# Booster1.net
KiCad netlist of a schematic drawn in EAGLE
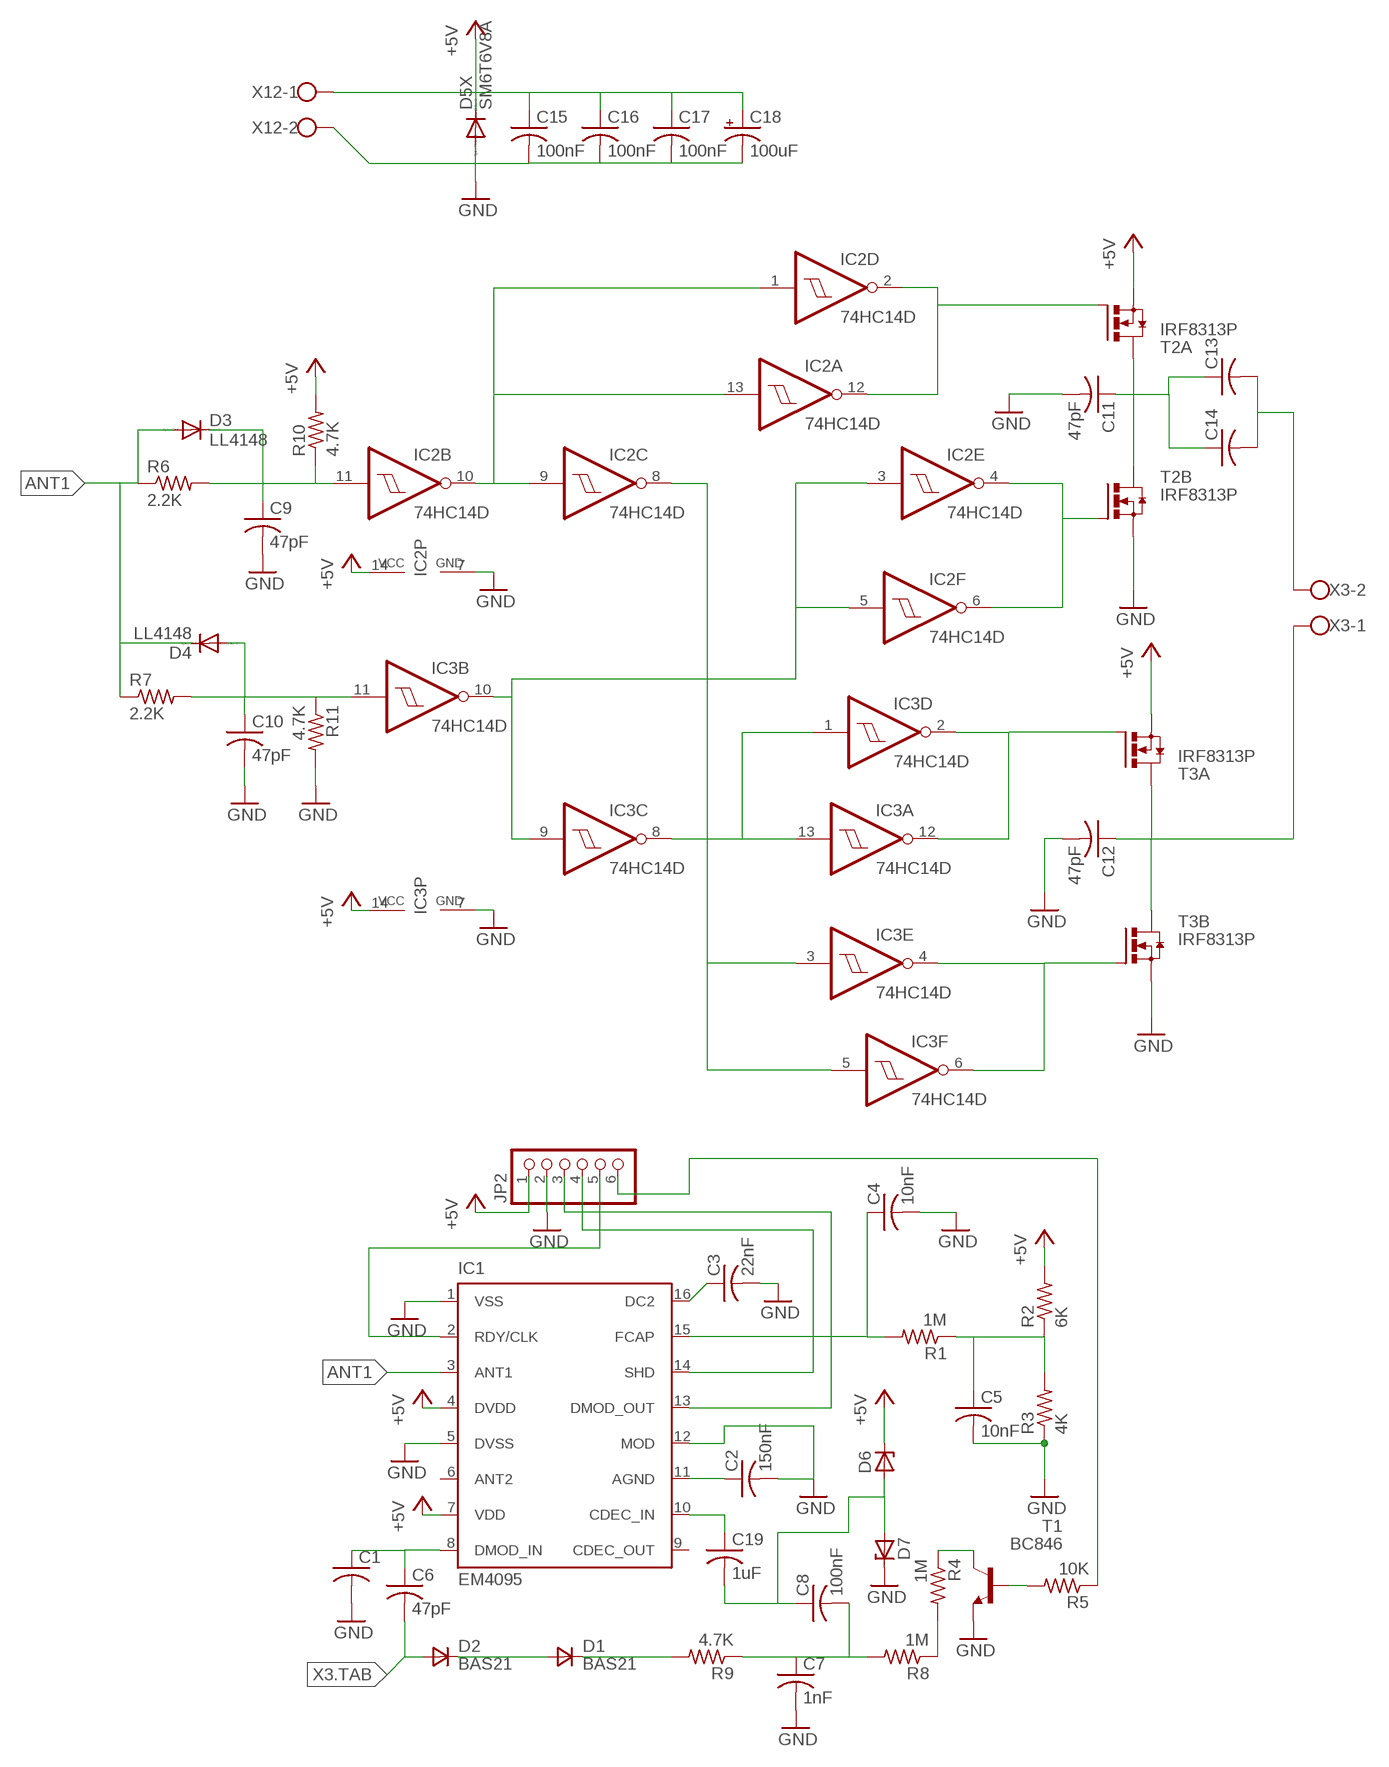
[diagram p0: schematic, sheet 1]

(export (version "E")
  (design (tool "Eeschema 10.0.6"))
  (components
    (comp (ref "C1")
      (value "C-USC1206K")
      (footprint "eagle-import:C1206K")
      (libsource (lib "eagle-import") (part "C-USC1206K"))
    )
    (comp (ref "C2")
      (value "150nF")
      (footprint "eagle-import:C1206")
      (libsource (lib "eagle-import") (part "C-USC1206"))
    )
    (comp (ref "C3")
      (value "22nF")
      (footprint "eagle-import:C1206K")
      (libsource (lib "eagle-import") (part "C-USC1206K"))
    )
    (comp (ref "C4")
      (value "10nF")
      (footprint "eagle-import:C1206K")
      (libsource (lib "eagle-import") (part "C-USC1206K"))
    )
    (comp (ref "C5")
      (value "10nF")
      (footprint "eagle-import:C1206K")
      (libsource (lib "eagle-import") (part "C-USC1206K"))
    )
    (comp (ref "C6")
      (value "47pF")
      (footprint "eagle-import:C050-025X075")
      (libsource (lib "eagle-import") (part "C-US050-025X075"))
    )
    (comp (ref "C7")
      (value "1nF")
      (footprint "eagle-import:C050-025X075")
      (libsource (lib "eagle-import") (part "C-US050-025X075"))
    )
    (comp (ref "C8")
      (value "100nF")
      (footprint "eagle-import:C050-025X075")
      (libsource (lib "eagle-import") (part "C-US050-025X075"))
    )
    (comp (ref "C9")
      (value "47pF")
      (footprint "eagle-import:C1206")
      (libsource (lib "eagle-import") (part "C-USC1206"))
    )
    (comp (ref "C10")
      (value "47pF")
      (footprint "eagle-import:C1206")
      (libsource (lib "eagle-import") (part "C-USC1206"))
    )
    (comp (ref "C11")
      (value "47pF")
      (footprint "eagle-import:C1206")
      (libsource (lib "eagle-import") (part "C-USC1206"))
    )
    (comp (ref "C12")
      (value "47pF")
      (footprint "eagle-import:C1206")
      (libsource (lib "eagle-import") (part "C-USC1206"))
    )
    (comp (ref "C13")
      (value "C-US050-025X075")
      (footprint "eagle-import:C050-025X075")
      (libsource (lib "eagle-import") (part "C-US050-025X075"))
    )
    (comp (ref "C14")
      (value "C-US050-025X075")
      (footprint "eagle-import:C050-025X075")
      (libsource (lib "eagle-import") (part "C-US050-025X075"))
    )
    (comp (ref "C15")
      (value "100nF")
      (footprint "eagle-import:C1206")
      (libsource (lib "eagle-import") (part "C-USC1206"))
    )
    (comp (ref "C16")
      (value "100nF")
      (footprint "eagle-import:C1206")
      (libsource (lib "eagle-import") (part "C-USC1206"))
    )
    (comp (ref "C17")
      (value "100nF")
      (footprint "eagle-import:C1206")
      (libsource (lib "eagle-import") (part "C-USC1206"))
    )
    (comp (ref "C18")
      (value "100uF")
      (footprint "eagle-import:CT7343")
      (libsource (lib "eagle-import") (part "CPOL-USCT7343"))
    )
    (comp (ref "C19")
      (value "1uF")
      (footprint "eagle-import:C050-025X075")
      (libsource (lib "eagle-import") (part "C-US050-025X075"))
    )
    (comp (ref "D1")
      (value "BAS21")
      (footprint "eagle-import:SOT-23")
      (libsource (lib "eagle-import") (part "VAR2SOT23"))
    )
    (comp (ref "D2")
      (value "BAS21")
      (footprint "eagle-import:SOT-23")
      (libsource (lib "eagle-import") (part "VAR2SOT23"))
    )
    (comp (ref "D3")
      (value "LL4148")
      (footprint "eagle-import:SOD106-R")
      (libsource (lib "eagle-import") (part "DIODE-SOD106-R"))
    )
    (comp (ref "D4")
      (value "LL4148")
      (footprint "eagle-import:SOD106-R")
      (libsource (lib "eagle-import") (part "DIODE-SOD106-R"))
    )
    (comp (ref "D5X")
      (value "SM6T6V8A")
      (footprint "eagle-import:SMB")
      (libsource (lib "eagle-import") (part "SM6T6V8A"))
    )
    (comp (ref "D6")
      (value "ZENER-DIODESMB")
      (footprint "eagle-import:SMB")
      (libsource (lib "eagle-import") (part "ZENER-DIODESMB"))
    )
    (comp (ref "D7")
      (value "ZENER-DIODESMB")
      (footprint "eagle-import:SMB")
      (libsource (lib "eagle-import") (part "ZENER-DIODESMB"))
    )
    (comp (ref "IC1")
      (value "EM4095")
      (footprint "eagle-import:SO16")
      (libsource (lib "eagle-import") (part "EM4095"))
    )
    (comp (ref "IC2")
      (value "74HC14D")
      (footprint "eagle-import:SO14")
      (libsource (lib "eagle-import") (part "7414DHC"))
    )
    (comp (ref "IC3")
      (value "74HC14D")
      (footprint "eagle-import:SO14")
      (libsource (lib "eagle-import") (part "7414DHC"))
    )
    (comp (ref "JP2")
      (value "PINHD-1X6")
      (footprint "eagle-import:1X06")
      (libsource (lib "eagle-import") (part "PINHD-1X6"))
    )
    (comp (ref "R1")
      (value "1M")
      (footprint "eagle-import:R1206")
      (libsource (lib "eagle-import") (part "R-US_R1206"))
    )
    (comp (ref "R2")
      (value "6K")
      (footprint "eagle-import:R1206")
      (libsource (lib "eagle-import") (part "R-US_R1206"))
    )
    (comp (ref "R3")
      (value "4K")
      (footprint "eagle-import:R1206")
      (libsource (lib "eagle-import") (part "R-US_R1206"))
    )
    (comp (ref "R4")
      (value "1M")
      (footprint "eagle-import:R1206")
      (libsource (lib "eagle-import") (part "R-US_R1206"))
    )
    (comp (ref "R5")
      (value "10K")
      (footprint "eagle-import:R1206")
      (libsource (lib "eagle-import") (part "R-US_R1206"))
    )
    (comp (ref "R6")
      (value "2.2K")
      (footprint "eagle-import:R1206")
      (libsource (lib "eagle-import") (part "R-US_R1206"))
    )
    (comp (ref "R7")
      (value "2.2K")
      (footprint "eagle-import:R1206")
      (libsource (lib "eagle-import") (part "R-US_R1206"))
    )
    (comp (ref "R8")
      (value "1M")
      (footprint "eagle-import:R1206")
      (libsource (lib "eagle-import") (part "R-US_R1206"))
    )
    (comp (ref "R9")
      (value "4.7K")
      (footprint "eagle-import:R1206")
      (libsource (lib "eagle-import") (part "R-US_R1206"))
    )
    (comp (ref "R10")
      (value "4.7K")
      (footprint "eagle-import:R1206")
      (libsource (lib "eagle-import") (part "R-US_R1206"))
    )
    (comp (ref "R11")
      (value "4.7K")
      (footprint "eagle-import:R1206")
      (libsource (lib "eagle-import") (part "R-US_R1206"))
    )
    (comp (ref "T1")
      (value "BC846")
      (footprint "eagle-import:SOT23")
      (libsource (lib "eagle-import") (part "BC846"))
    )
    (comp (ref "T2")
      (value "IRF8313P")
      (footprint "eagle-import:SO-08")
      (libsource (lib "eagle-import") (part "IRF8313P"))
    )
    (comp (ref "T3")
      (value "IRF8313P")
      (footprint "eagle-import:SO-08")
      (libsource (lib "eagle-import") (part "IRF8313P"))
    )
    (comp (ref "X3")
      (value "W237-102")
      (footprint "eagle-import:W237-102")
      (fields (field (name "MPN") "237-102"))
      (libsource (lib "eagle-import") (part "W237-102"))
    )
    (comp (ref "X12")
      (value "W237-102")
      (footprint "eagle-import:W237-102")
      (fields (field (name "MPN") "237-102"))
      (libsource (lib "eagle-import") (part "W237-102"))
    )
  )
  (nets
    (net (code "1") (name "+5V") (class "Default")
      (node (ref "C15") (pin "1") (pinfunction "1_1") (pintype "passive"))
      (node (ref "C16") (pin "1") (pinfunction "1_1") (pintype "passive"))
      (node (ref "C17") (pin "1") (pinfunction "1_1") (pintype "passive"))
      (node (ref "C18") (pin "+") (pinfunction "+_+") (pintype "passive"))
      (node (ref "D5X") (pin "C") (pinfunction "C_C") (pintype "passive"))
      (node (ref "D6") (pin "C") (pinfunction "C_C") (pintype "passive"))
      (node (ref "IC1") (pin "4") (pinfunction "DVDD_4") (pintype "power_in"))
      (node (ref "IC1") (pin "7") (pinfunction "VDD_7") (pintype "power_in"))
      (node (ref "IC2") (pin "14") (pinfunction "VCC_14") (pintype "power_in"))
      (node (ref "IC3") (pin "14") (pinfunction "VCC_14") (pintype "power_in"))
      (node (ref "JP2") (pin "1") (pinfunction "1_1") (pintype "passive"))
      (node (ref "R10") (pin "2") (pinfunction "2_2") (pintype "passive"))
      (node (ref "R2") (pin "2") (pinfunction "2_2") (pintype "passive"))
      (node (ref "T2") (pin "3") (pinfunction "S_3") (pintype "passive"))
      (node (ref "T3") (pin "3") (pinfunction "S_3") (pintype "passive"))
      (node (ref "X12") (pin "1") (pinfunction "KL_1") (pintype "passive"))
    )
    (net (code "2") (name "ANT1") (class "Default")
      (node (ref "D3") (pin "A") (pinfunction "A_A") (pintype "passive"))
      (node (ref "D4") (pin "C") (pinfunction "C_C") (pintype "passive"))
      (node (ref "IC1") (pin "3") (pinfunction "ANT1_3") (pintype "passive"))
      (node (ref "R6") (pin "1") (pinfunction "1_1") (pintype "passive"))
      (node (ref "R7") (pin "1") (pinfunction "1_1") (pintype "passive"))
    )
    (net (code "3") (name "GND") (class "Default")
      (node (ref "C1") (pin "2") (pinfunction "2_2") (pintype "passive"))
      (node (ref "C10") (pin "2") (pinfunction "2_2") (pintype "passive"))
      (node (ref "C11") (pin "2") (pinfunction "2_2") (pintype "passive"))
      (node (ref "C12") (pin "2") (pinfunction "2_2") (pintype "passive"))
      (node (ref "C15") (pin "2") (pinfunction "2_2") (pintype "passive"))
      (node (ref "C16") (pin "2") (pinfunction "2_2") (pintype "passive"))
      (node (ref "C17") (pin "2") (pinfunction "2_2") (pintype "passive"))
      (node (ref "C18") (pin "-") (pinfunction "-_-") (pintype "passive"))
      (node (ref "C2") (pin "2") (pinfunction "2_2") (pintype "passive"))
      (node (ref "C3") (pin "2") (pinfunction "2_2") (pintype "passive"))
      (node (ref "C4") (pin "2") (pinfunction "2_2") (pintype "passive"))
      (node (ref "C5") (pin "2") (pinfunction "2_2") (pintype "passive"))
      (node (ref "C7") (pin "2") (pinfunction "2_2") (pintype "passive"))
      (node (ref "C9") (pin "2") (pinfunction "2_2") (pintype "passive"))
      (node (ref "D5X") (pin "A") (pinfunction "A_A") (pintype "passive"))
      (node (ref "D7") (pin "C") (pinfunction "C_C") (pintype "passive"))
      (node (ref "IC1") (pin "1") (pinfunction "VSS_1") (pintype "power_in"))
      (node (ref "IC1") (pin "12") (pinfunction "MOD_12") (pintype "input"))
      (node (ref "IC1") (pin "5") (pinfunction "DVSS_5") (pintype "power_in"))
      (node (ref "IC2") (pin "7") (pinfunction "GND_7") (pintype "power_in"))
      (node (ref "IC3") (pin "7") (pinfunction "GND_7") (pintype "power_in"))
      (node (ref "JP2") (pin "2") (pinfunction "2_2") (pintype "passive"))
      (node (ref "R11") (pin "2") (pinfunction "2_2") (pintype "passive"))
      (node (ref "R3") (pin "1") (pinfunction "1_1") (pintype "passive"))
      (node (ref "T1") (pin "2") (pinfunction "E_2") (pintype "passive"))
      (node (ref "T2") (pin "1") (pinfunction "S_1") (pintype "passive"))
      (node (ref "T3") (pin "1") (pinfunction "S_1") (pintype "passive"))
      (node (ref "X12") (pin "2") (pinfunction "KL_2") (pintype "passive"))
    )
    (net (code "4") (name "Net-(C5-Pad1)") (class "Default")
      (node (ref "C5") (pin "1") (pinfunction "1_1") (pintype "passive"))
      (node (ref "R1") (pin "1") (pinfunction "1_1") (pintype "passive"))
      (node (ref "R2") (pin "1") (pinfunction "1_1") (pintype "passive"))
      (node (ref "R3") (pin "2") (pinfunction "2_2") (pintype "passive"))
    )
    (net (code "5") (name "Net-(C7-Pad1)") (class "Default")
      (node (ref "C7") (pin "1") (pinfunction "1_1") (pintype "passive"))
      (node (ref "C8") (pin "2") (pinfunction "2_2") (pintype "passive"))
      (node (ref "R8") (pin "2") (pinfunction "2_2") (pintype "passive"))
      (node (ref "R9") (pin "1") (pinfunction "1_1") (pintype "passive"))
    )
    (net (code "6") (name "Net-(C11-Pad1)") (class "Default")
      (node (ref "C11") (pin "1") (pinfunction "1_1") (pintype "passive"))
      (node (ref "C13") (pin "1") (pinfunction "1_1") (pintype "passive"))
      (node (ref "C14") (pin "1") (pinfunction "1_1") (pintype "passive"))
      (node (ref "T2") (pin "5") (pinfunction "D_5") (pintype "passive"))
      (node (ref "T2") (pin "6") (pinfunction "D_6") (pintype "passive"))
      (node (ref "T2") (pin "7") (pinfunction "D_7") (pintype "passive"))
      (node (ref "T2") (pin "8") (pinfunction "D_8") (pintype "passive"))
    )
    (net (code "7") (name "Net-(C19-Pad2)") (class "Default")
      (node (ref "C19") (pin "2") (pinfunction "2_2") (pintype "passive"))
      (node (ref "C8") (pin "1") (pinfunction "1_1") (pintype "passive"))
      (node (ref "D6") (pin "A") (pinfunction "A_A") (pintype "passive"))
      (node (ref "D7") (pin "A") (pinfunction "A_A") (pintype "passive"))
    )
    (net (code "8") (name "Net-(D1-A)") (class "Default")
      (node (ref "D1") (pin "3") (pinfunction "A_3") (pintype "passive"))
      (node (ref "D2") (pin "1") (pinfunction "C_1") (pintype "passive"))
    )
    (net (code "9") (name "Net-(D1-C)") (class "Default")
      (node (ref "D1") (pin "1") (pinfunction "C_1") (pintype "passive"))
      (node (ref "R9") (pin "2") (pinfunction "2_2") (pintype "passive"))
    )
    (net (code "10") (name "Net-(IC1-AGND)") (class "Default")
      (node (ref "C2") (pin "1") (pinfunction "1_1") (pintype "passive"))
      (node (ref "IC1") (pin "11") (pinfunction "AGND_11") (pintype "power_in"))
    )
    (net (code "11") (name "Net-(IC1-CDEC_IN)") (class "Default")
      (node (ref "C19") (pin "1") (pinfunction "1_1") (pintype "passive"))
      (node (ref "IC1") (pin "10") (pinfunction "CDEC_IN_10") (pintype "input"))
    )
    (net (code "12") (name "Net-(IC1-DC2)") (class "Default")
      (node (ref "C3") (pin "1") (pinfunction "1_1") (pintype "passive"))
      (node (ref "IC1") (pin "16") (pinfunction "DC2_16") (pintype "passive"))
    )
    (net (code "13") (name "Net-(IC1-DMOD_IN)") (class "Default")
      (node (ref "C1") (pin "1") (pinfunction "1_1") (pintype "passive"))
      (node (ref "C6") (pin "1") (pinfunction "1_1") (pintype "passive"))
      (node (ref "IC1") (pin "8") (pinfunction "DMOD_IN_8") (pintype "input"))
    )
    (net (code "14") (name "Net-(IC1-DMOD_OUT)") (class "Default")
      (node (ref "IC1") (pin "13") (pinfunction "DMOD_OUT_13") (pintype "output"))
      (node (ref "JP2") (pin "3") (pinfunction "3_3") (pintype "passive"))
    )
    (net (code "15") (name "Net-(IC1-FCAP)") (class "Default")
      (node (ref "C4") (pin "1") (pinfunction "1_1") (pintype "passive"))
      (node (ref "IC1") (pin "15") (pinfunction "FCAP_15") (pintype "passive"))
      (node (ref "R1") (pin "2") (pinfunction "2_2") (pintype "passive"))
    )
    (net (code "16") (name "Net-(IC1-RDY{slash}CLK)") (class "Default")
      (node (ref "IC1") (pin "2") (pinfunction "RDY/CLK_2") (pintype "output"))
      (node (ref "JP2") (pin "5") (pinfunction "5_5") (pintype "passive"))
    )
    (net (code "17") (name "Net-(IC1-SHD)") (class "Default")
      (node (ref "IC1") (pin "14") (pinfunction "SHD_14") (pintype "input"))
      (node (ref "JP2") (pin "4") (pinfunction "4_4") (pintype "passive"))
    )
    (net (code "18") (name "Net-(IC2A-I)") (class "Default")
      (node (ref "IC2") (pin "1") (pinfunction "I_1") (pintype "input"))
      (node (ref "IC2") (pin "10") (pinfunction "O_10") (pintype "output"))
      (node (ref "IC2") (pin "13") (pinfunction "I_13") (pintype "input"))
      (node (ref "IC2") (pin "9") (pinfunction "I_9") (pintype "input"))
    )
    (net (code "19") (name "Net-(IC2A-O)") (class "Default")
      (node (ref "IC2") (pin "12") (pinfunction "O_12") (pintype "output"))
      (node (ref "IC2") (pin "2") (pinfunction "O_2") (pintype "output"))
      (node (ref "T2") (pin "4") (pinfunction "G_4") (pintype "passive"))
    )
    (net (code "20") (name "Net-(IC2B-I)") (class "Default")
      (node (ref "C9") (pin "1") (pinfunction "1_1") (pintype "passive"))
      (node (ref "D3") (pin "C") (pinfunction "C_C") (pintype "passive"))
      (node (ref "IC2") (pin "11") (pinfunction "I_11") (pintype "input"))
      (node (ref "R10") (pin "1") (pinfunction "1_1") (pintype "passive"))
      (node (ref "R6") (pin "2") (pinfunction "2_2") (pintype "passive"))
    )
    (net (code "21") (name "Net-(IC2C-O)") (class "Default")
      (node (ref "IC2") (pin "8") (pinfunction "O_8") (pintype "output"))
      (node (ref "IC3") (pin "3") (pinfunction "I_3") (pintype "input"))
      (node (ref "IC3") (pin "5") (pinfunction "I_5") (pintype "input"))
    )
    (net (code "22") (name "Net-(IC2E-I)") (class "Default")
      (node (ref "IC2") (pin "3") (pinfunction "I_3") (pintype "input"))
      (node (ref "IC2") (pin "5") (pinfunction "I_5") (pintype "input"))
      (node (ref "IC3") (pin "10") (pinfunction "O_10") (pintype "output"))
      (node (ref "IC3") (pin "9") (pinfunction "I_9") (pintype "input"))
    )
    (net (code "23") (name "Net-(IC2E-O)") (class "Default")
      (node (ref "IC2") (pin "4") (pinfunction "O_4") (pintype "output"))
      (node (ref "IC2") (pin "6") (pinfunction "O_6") (pintype "output"))
      (node (ref "T2") (pin "2") (pinfunction "G_2") (pintype "passive"))
    )
    (net (code "24") (name "Net-(IC3A-I)") (class "Default")
      (node (ref "IC3") (pin "1") (pinfunction "I_1") (pintype "input"))
      (node (ref "IC3") (pin "13") (pinfunction "I_13") (pintype "input"))
      (node (ref "IC3") (pin "8") (pinfunction "O_8") (pintype "output"))
    )
    (net (code "25") (name "Net-(IC3A-O)") (class "Default")
      (node (ref "IC3") (pin "12") (pinfunction "O_12") (pintype "output"))
      (node (ref "IC3") (pin "2") (pinfunction "O_2") (pintype "output"))
      (node (ref "T3") (pin "4") (pinfunction "G_4") (pintype "passive"))
    )
    (net (code "26") (name "Net-(IC3B-I)") (class "Default")
      (node (ref "C10") (pin "1") (pinfunction "1_1") (pintype "passive"))
      (node (ref "D4") (pin "A") (pinfunction "A_A") (pintype "passive"))
      (node (ref "IC3") (pin "11") (pinfunction "I_11") (pintype "input"))
      (node (ref "R11") (pin "1") (pinfunction "1_1") (pintype "passive"))
      (node (ref "R7") (pin "2") (pinfunction "2_2") (pintype "passive"))
    )
    (net (code "27") (name "Net-(IC3E-O)") (class "Default")
      (node (ref "IC3") (pin "4") (pinfunction "O_4") (pintype "output"))
      (node (ref "IC3") (pin "6") (pinfunction "O_6") (pintype "output"))
      (node (ref "T3") (pin "2") (pinfunction "G_2") (pintype "passive"))
    )
    (net (code "28") (name "Net-(JP2-Pad6)") (class "Default")
      (node (ref "JP2") (pin "6") (pinfunction "6_6") (pintype "passive"))
      (node (ref "R5") (pin "1") (pinfunction "1_1") (pintype "passive"))
    )
    (net (code "29") (name "Net-(R4-Pad2)") (class "Default")
      (node (ref "R4") (pin "2") (pinfunction "2_2") (pintype "passive"))
      (node (ref "R8") (pin "1") (pinfunction "1_1") (pintype "passive"))
    )
    (net (code "30") (name "Net-(T1-B)") (class "Default")
      (node (ref "R5") (pin "2") (pinfunction "2_2") (pintype "passive"))
      (node (ref "T1") (pin "1") (pinfunction "B_1") (pintype "passive"))
    )
    (net (code "31") (name "Net-(T1-C)") (class "Default")
      (node (ref "R4") (pin "1") (pinfunction "1_1") (pintype "passive"))
      (node (ref "T1") (pin "3") (pinfunction "C_3") (pintype "passive"))
    )
    (net (code "32") (name "Net-(X3A-KL)") (class "Default")
      (node (ref "C12") (pin "1") (pinfunction "1_1") (pintype "passive"))
      (node (ref "T3") (pin "5") (pinfunction "D_5") (pintype "passive"))
      (node (ref "T3") (pin "6") (pinfunction "D_6") (pintype "passive"))
      (node (ref "T3") (pin "7") (pinfunction "D_7") (pintype "passive"))
      (node (ref "T3") (pin "8") (pinfunction "D_8") (pintype "passive"))
      (node (ref "X3") (pin "1") (pinfunction "KL_1") (pintype "passive"))
    )
    (net (code "33") (name "X3.TAB") (class "Default")
      (node (ref "C13") (pin "2") (pinfunction "2_2") (pintype "passive"))
      (node (ref "C14") (pin "2") (pinfunction "2_2") (pintype "passive"))
      (node (ref "C6") (pin "2") (pinfunction "2_2") (pintype "passive"))
      (node (ref "D2") (pin "3") (pinfunction "A_3") (pintype "passive"))
      (node (ref "X3") (pin "2") (pinfunction "KL_2") (pintype "passive"))
    )
    (net (code "34") (name "unconnected-(IC1-ANT2-Pad6)") (class "Default")
      (node (ref "IC1") (pin "6") (pinfunction "ANT2_6") (pintype "passive"))
    )
    (net (code "35") (name "unconnected-(IC1-CDEC_OUT-Pad9)") (class "Default")
      (node (ref "IC1") (pin "9") (pinfunction "CDEC_OUT_9") (pintype "output"))
    )
  )
)
